# JTAG.net
KiCad netlist of a schematic drawn in Altium Designer
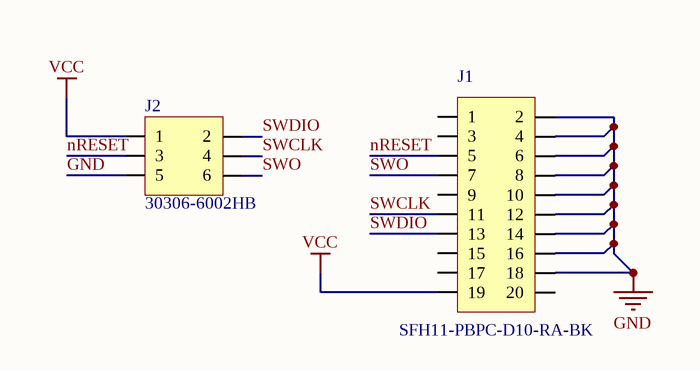
[diagram p0: JTAG.SchDoc]

(export (version "E")
  (design (tool "Eeschema 10.0.6"))
  (components
    (comp (ref "J1")
      (value "SFH11-PBPC-D10-RA-BK")
      (footprint "SFH11-PBPC-D10-RA-BK")
      (description "20 Position Header Connector 0.100\" (2.54mm) Through Hole, Right Angle Gold")
      (fields (field (name "MANUFACTURER") "Sullins Connector Solutions"))
      (libsource (lib "Headers") (part "SFH11-PBPC-D10-RA-BK"))
    )
    (comp (ref "J2")
      (value "30306-6002HB")
      (footprint "30306-6002HB")
      (description "6 Positions Header Connector 0.100\" (2.54mm) Through Hole Gold")
      (fields (field (name "MANUFACTURER") "3M"))
      (libsource (lib "Headers") (part "30306-6002HB"))
    )
  )
  (nets
    (net (code "1") (name "/SWCLK") (class "Default")
      (node (ref "J1") (pin "11") (pinfunction "11_11") (pintype "passive"))
      (node (ref "J2") (pin "4") (pinfunction "4_4") (pintype "passive"))
    )
    (net (code "2") (name "/SWDIO") (class "Default")
      (node (ref "J1") (pin "13") (pinfunction "13_13") (pintype "passive"))
      (node (ref "J2") (pin "2") (pinfunction "2_2") (pintype "passive"))
    )
    (net (code "3") (name "/SWO") (class "Default")
      (node (ref "J1") (pin "7") (pinfunction "7_7") (pintype "passive"))
      (node (ref "J2") (pin "6") (pinfunction "6_6") (pintype "passive"))
    )
    (net (code "4") (name "/nRESET") (class "Default")
      (node (ref "J1") (pin "5") (pinfunction "5_5") (pintype "passive"))
      (node (ref "J2") (pin "3") (pinfunction "3_3") (pintype "passive"))
    )
    (net (code "5") (name "GND") (class "Default")
      (node (ref "J1") (pin "10") (pinfunction "10_10") (pintype "passive"))
      (node (ref "J1") (pin "12") (pinfunction "12_12") (pintype "passive"))
      (node (ref "J1") (pin "14") (pinfunction "14_14") (pintype "passive"))
      (node (ref "J1") (pin "16") (pinfunction "16_16") (pintype "passive"))
      (node (ref "J1") (pin "18") (pinfunction "18_18") (pintype "passive"))
      (node (ref "J1") (pin "2") (pinfunction "2_2") (pintype "passive"))
      (node (ref "J1") (pin "4") (pinfunction "4_4") (pintype "passive"))
      (node (ref "J1") (pin "6") (pinfunction "6_6") (pintype "passive"))
      (node (ref "J1") (pin "8") (pinfunction "8_8") (pintype "passive"))
      (node (ref "J2") (pin "5") (pinfunction "5_5") (pintype "passive"))
    )
    (net (code "6") (name "VCC") (class "Default")
      (node (ref "J1") (pin "19") (pinfunction "19_19") (pintype "passive"))
      (node (ref "J2") (pin "1") (pinfunction "1_1") (pintype "passive"))
    )
    (net (code "7") (name "unconnected-(J1-Pad1)") (class "Default")
      (node (ref "J1") (pin "1") (pinfunction "1_1") (pintype "passive"))
    )
    (net (code "8") (name "unconnected-(J1-Pad3)") (class "Default")
      (node (ref "J1") (pin "3") (pinfunction "3_3") (pintype "passive"))
    )
    (net (code "9") (name "unconnected-(J1-Pad9)") (class "Default")
      (node (ref "J1") (pin "9") (pinfunction "9_9") (pintype "passive"))
    )
    (net (code "10") (name "unconnected-(J1-Pad15)") (class "Default")
      (node (ref "J1") (pin "15") (pinfunction "15_15") (pintype "passive"))
    )
    (net (code "11") (name "unconnected-(J1-Pad17)") (class "Default")
      (node (ref "J1") (pin "17") (pinfunction "17_17") (pintype "passive"))
    )
    (net (code "12") (name "unconnected-(J1-Pad20)") (class "Default")
      (node (ref "J1") (pin "20") (pinfunction "20_20") (pintype "passive"))
    )
  )
)
